# meteo-slave.net
KiCad netlist of a schematic drawn in EAGLE
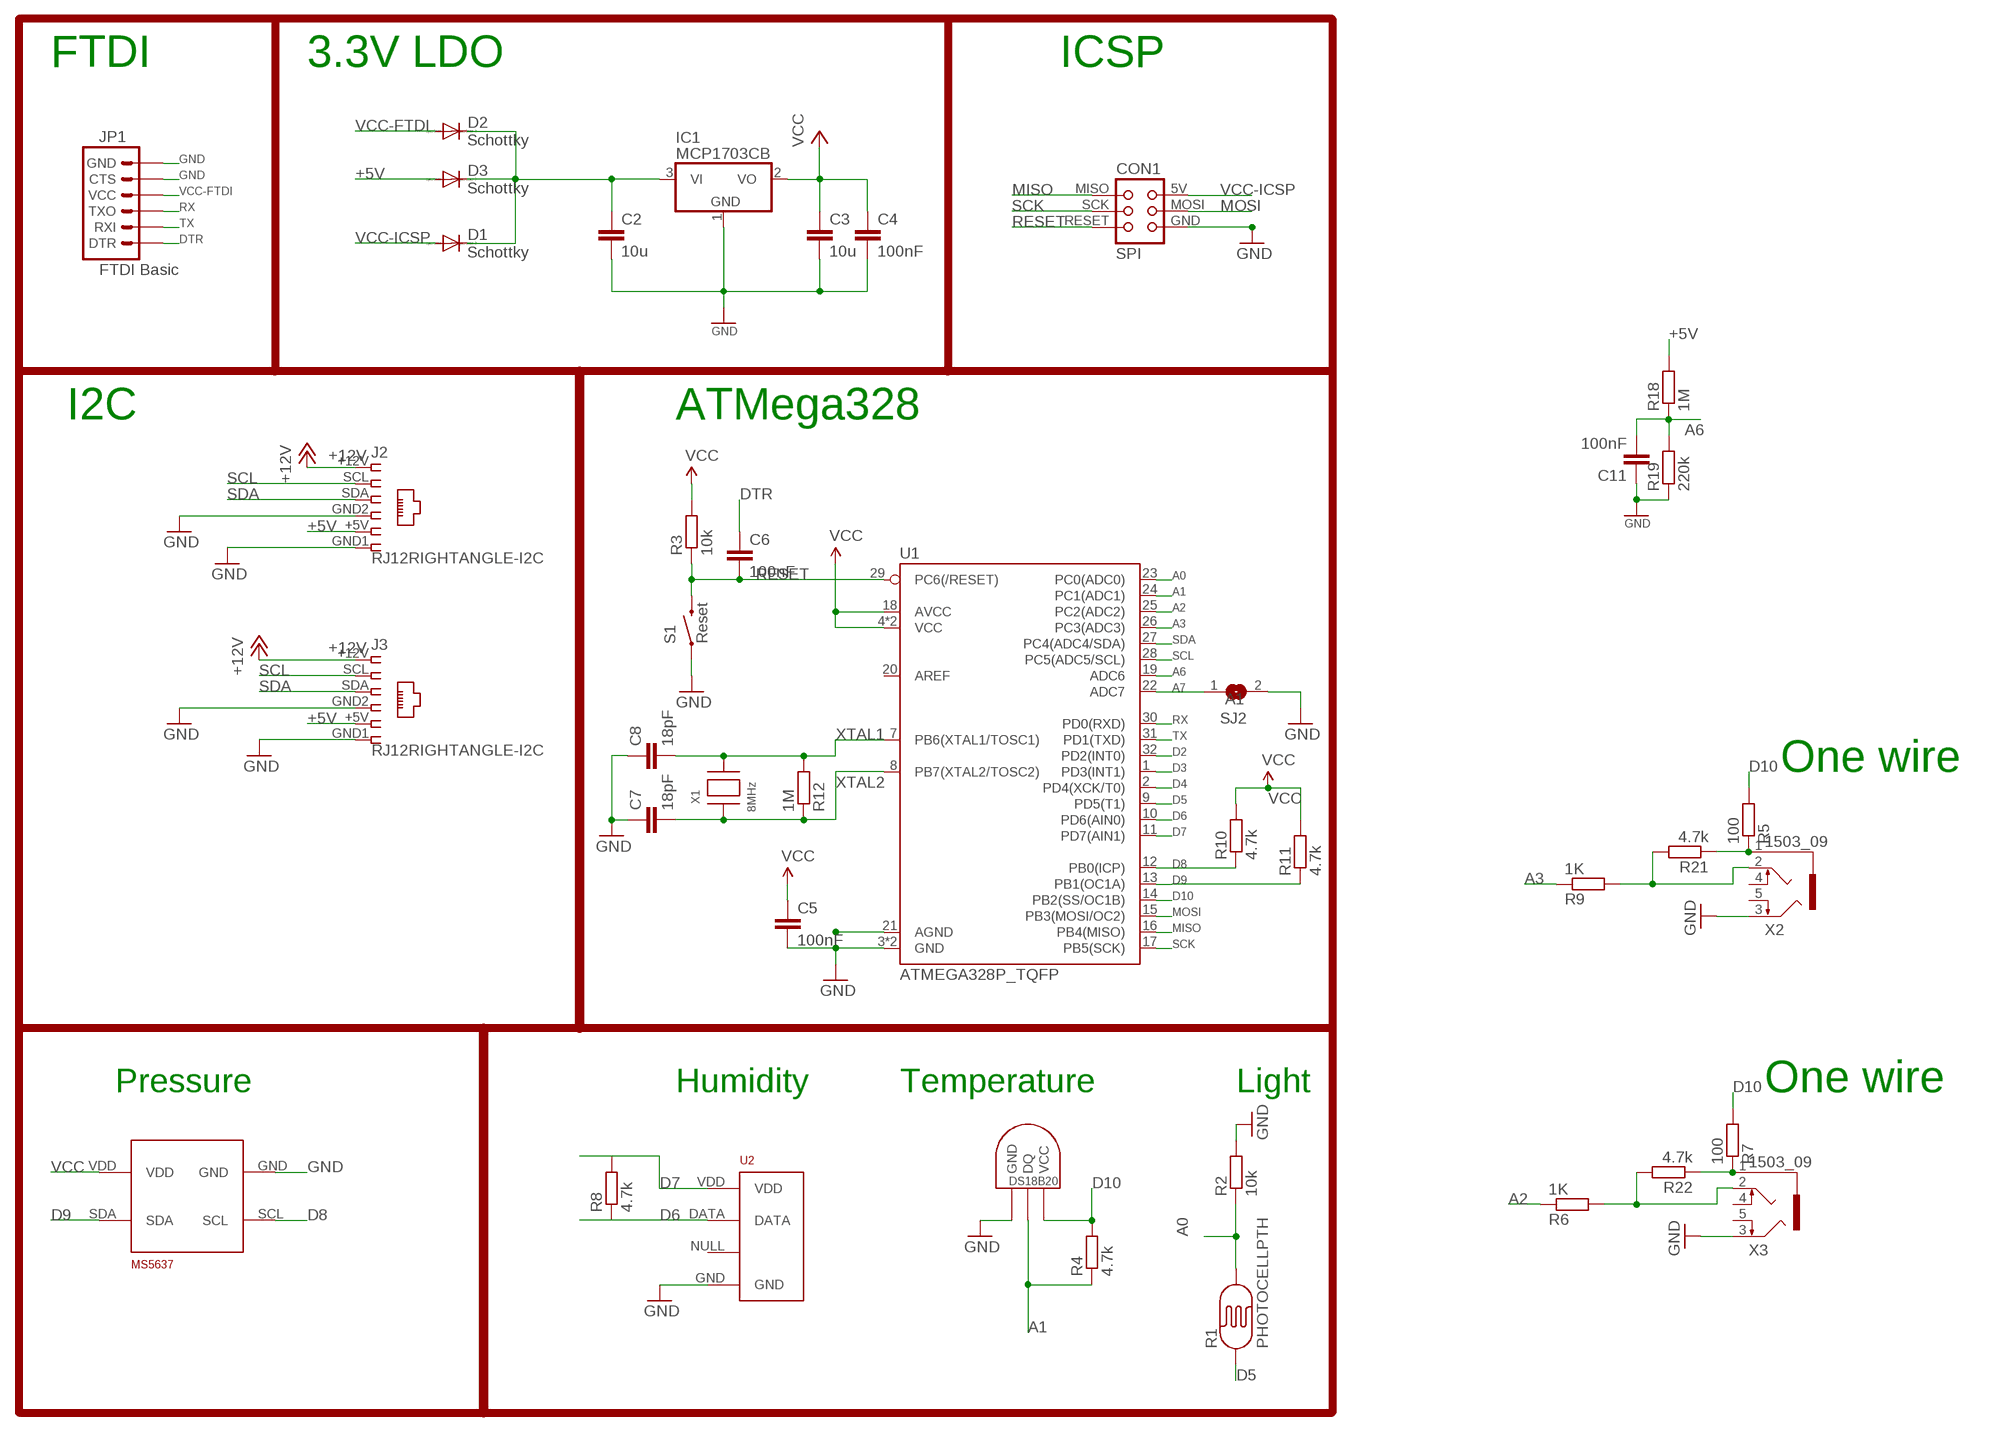
[diagram p0: schematic, sheet 1]

(export (version "E")
  (design (tool "Eeschema 10.0.6"))
  (components
    (comp (ref "C2")
      (value "10u")
      (footprint "eagle-import:C0805K")
      (fields (field (name "MPN") "77-VJ1206V106ZXQTBC"))
      (libsource (lib "eagle-import") (part "C-EUC0805K"))
    )
    (comp (ref "C3")
      (value "10u")
      (footprint "eagle-import:C0805K")
      (fields (field (name "MPN") "77-VJ1206V106ZXQTBC"))
      (libsource (lib "eagle-import") (part "C-EUC0805K"))
    )
    (comp (ref "C4")
      (value "100nF")
      (footprint "eagle-import:C0805K")
      (fields (field (name "MPN") "80-C1206C104K5R"))
      (libsource (lib "eagle-import") (part "C-EUC0805K"))
    )
    (comp (ref "C5")
      (value "100nF")
      (footprint "eagle-import:C0805K")
      (fields (field (name "MPN") "80-C1206C104K5R"))
      (libsource (lib "eagle-import") (part "C-EUC0805K"))
    )
    (comp (ref "C6")
      (value "100nF")
      (footprint "eagle-import:C0805K")
      (fields (field (name "MPN") "80-C1206C104K5R"))
      (libsource (lib "eagle-import") (part "C-EUC0805K"))
    )
    (comp (ref "C7")
      (value "18pF")
      (footprint "eagle-import:C0805K")
      (fields (field (name "MPN") "77-VJ1206A180JXXPBC"))
      (libsource (lib "eagle-import") (part "C-EUC0805K"))
    )
    (comp (ref "C8")
      (value "18pF")
      (footprint "eagle-import:C0805K")
      (fields (field (name "MPN") "77-VJ1206A180JXXPBC"))
      (libsource (lib "eagle-import") (part "C-EUC0805K"))
    )
    (comp (ref "C11")
      (value "100nF")
      (footprint "eagle-import:C0805K")
      (fields (field (name "MPN") "80-C1206C104K5R"))
      (libsource (lib "eagle-import") (part "C-EUC0805K"))
    )
    (comp (ref "CON1")
      (value "SPI")
      (footprint "eagle-import:TC2030-MCP")
      (libsource (lib "eagle-import") (part "TINYISPTAG"))
    )
    (comp (ref "D1")
      (value "Schottky")
      (footprint "eagle-import:SOD123")
      (fields (field (name "MPN") "621-1N5819HW-F"))
      (libsource (lib "eagle-import") (part "MBR0520LT"))
    )
    (comp (ref "D2")
      (value "Schottky")
      (footprint "eagle-import:SOD123")
      (fields (field (name "MPN") "621-1N5819HW-F"))
      (libsource (lib "eagle-import") (part "MBR0520LT"))
    )
    (comp (ref "D3")
      (value "Schottky")
      (footprint "eagle-import:SOD123")
      (fields (field (name "MPN") "621-1N5819HW-F"))
      (libsource (lib "eagle-import") (part "MBR0520LT"))
    )
    (comp (ref "IC1")
      (value "MCP1703CB")
      (footprint "eagle-import:SOT23")
      (libsource (lib "eagle-import") (part "MCP1703CB"))
    )
    (comp (ref "J2")
      (value "RJ12RIGHTANGLE-I2C")
      (footprint "eagle-import:RJ12-RIGHTANGLE-I2C")
      (libsource (lib "eagle-import") (part "RJ12RIGHTANGLE-I2C"))
    )
    (comp (ref "J3")
      (value "RJ12RIGHTANGLE-I2C")
      (footprint "eagle-import:RJ12-RIGHTANGLE-I2C")
      (libsource (lib "eagle-import") (part "RJ12RIGHTANGLE-I2C"))
    )
    (comp (ref "JP1")
      (value "FTDI Basic")
      (footprint "eagle-import:1X06")
      (libsource (lib "eagle-import") (part "ARDUINO_SERIAL_PROGRAMPTH"))
    )
    (comp (ref "R1")
      (value "PHOTOCELLPTH")
      (footprint "eagle-import:PHOTOCELL")
      (libsource (lib "eagle-import") (part "PHOTOCELLPTH"))
    )
    (comp (ref "R2")
      (value "10k")
      (footprint "eagle-import:R0805")
      (libsource (lib "eagle-import") (part "resistor_348_R-EU_R0805"))
    )
    (comp (ref "R3")
      (value "10k")
      (footprint "eagle-import:R0805")
      (libsource (lib "eagle-import") (part "R-EU_R0805"))
    )
    (comp (ref "R4")
      (value "4.7k")
      (footprint "eagle-import:R0805")
      (libsource (lib "eagle-import") (part "resistor_348_R-EU_R0805"))
    )
    (comp (ref "R5")
      (value "100")
      (footprint "eagle-import:R0805")
      (libsource (lib "eagle-import") (part "R-EU_R0805"))
    )
    (comp (ref "R6")
      (value "1K")
      (footprint "eagle-import:R0805")
      (libsource (lib "eagle-import") (part "R-EU_R0805"))
    )
    (comp (ref "R7")
      (value "100")
      (footprint "eagle-import:R0805")
      (libsource (lib "eagle-import") (part "R-EU_R0805"))
    )
    (comp (ref "R8")
      (value "4.7k")
      (footprint "eagle-import:R0805")
      (libsource (lib "eagle-import") (part "resistor_348_R-EU_R0805"))
    )
    (comp (ref "R9")
      (value "1K")
      (footprint "eagle-import:R0805")
      (libsource (lib "eagle-import") (part "R-EU_R0805"))
    )
    (comp (ref "R10")
      (value "4.7k")
      (footprint "eagle-import:R0805")
      (libsource (lib "eagle-import") (part "resistor_348_R-EU_R0805"))
    )
    (comp (ref "R11")
      (value "4.7k")
      (footprint "eagle-import:R0805")
      (libsource (lib "eagle-import") (part "resistor_348_R-EU_R0805"))
    )
    (comp (ref "R12")
      (value "1M")
      (footprint "eagle-import:R0805")
      (libsource (lib "eagle-import") (part "R-EU_R0805"))
    )
    (comp (ref "R18")
      (value "1M")
      (footprint "eagle-import:R0805")
      (libsource (lib "eagle-import") (part "R-EU_R0805"))
    )
    (comp (ref "R19")
      (value "220k")
      (footprint "eagle-import:R0805")
      (libsource (lib "eagle-import") (part "R-EU_R0805"))
    )
    (comp (ref "R21")
      (value "4.7k")
      (footprint "eagle-import:R0805")
      (libsource (lib "eagle-import") (part "resistor_R-EU_R0805"))
    )
    (comp (ref "R22")
      (value "4.7k")
      (footprint "eagle-import:R0805")
      (libsource (lib "eagle-import") (part "resistor_R-EU_R0805"))
    )
    (comp (ref "S1")
      (value "Reset")
      (footprint "eagle-import:TACTILE-SWITCH-SMD-ALT01")
      (libsource (lib "eagle-import") (part "SWITCH-MOMENTARY-2SMD-ALT01"))
    )
    (comp (ref "SJ2") (value "A1") (footprint "eagle-import:SJ") (libsource (lib "eagle-import") (part "SJ")))
    (comp (ref "U$1")
      (value "DS1820TO92")
      (footprint "eagle-import:DS1820")
      (libsource (lib "eagle-import") (part "DS1820TO92"))
    )
    (comp (ref "U$19")
      (value "MS5637WIDE")
      (footprint "eagle-import:MS5637WIDE")
      (libsource (lib "eagle-import") (part "MS5637WIDE"))
    )
    (comp (ref "U1")
      (value "ATMEGA328P_TQFP")
      (footprint "eagle-import:TQFP32-08")
      (libsource (lib "eagle-import") (part "ATMEGA328P_TQFP"))
    )
    (comp (ref "U2")
      (value "RHT03_DHT-22_AM2302")
      (footprint "eagle-import:RHT03_DHT-22")
      (libsource (lib "eagle-import") (part "RHT03_DHT-22_AM2302"))
    )
    (comp (ref "X1")
      (value "8MHz")
      (footprint "eagle-import:NX6035")
      (fields (field (name "MPN") "729-F60800010"))
      (libsource (lib "eagle-import") (part "XTALNX6035"))
    )
    (comp (ref "X2")
      (value "1503_09")
      (footprint "eagle-import:1503_09")
      (libsource (lib "eagle-import") (part "1503_09"))
    )
    (comp (ref "X3")
      (value "1503_09")
      (footprint "eagle-import:1503_09")
      (libsource (lib "eagle-import") (part "1503_09"))
    )
  )
  (nets
    (net (code "1") (name "+5V") (class "Default")
      (node (ref "D3") (pin "A") (pinfunction "A_A") (pintype "passive"))
      (node (ref "J2") (pin "+5V") (pinfunction "5_+5V") (pintype "bidirectional"))
      (node (ref "J3") (pin "+5V") (pinfunction "5_+5V") (pintype "bidirectional"))
      (node (ref "R18") (pin "2") (pinfunction "2_2") (pintype "passive"))
    )
    (net (code "2") (name "+12V") (class "Default")
      (node (ref "J2") (pin "+12V") (pinfunction "1_+12V") (pintype "bidirectional"))
      (node (ref "J3") (pin "+12V") (pinfunction "1_+12V") (pintype "bidirectional"))
    )
    (net (code "3") (name "A0") (class "Default")
      (node (ref "R1") (pin "2") (pinfunction "P$2_2") (pintype "bidirectional"))
      (node (ref "R2") (pin "1") (pinfunction "1_1") (pintype "passive"))
      (node (ref "U1") (pin "23") (pinfunction "PC0(ADC0)_23") (pintype "bidirectional"))
    )
    (net (code "4") (name "A1") (class "Default")
      (node (ref "R4") (pin "1") (pinfunction "1_1") (pintype "passive"))
      (node (ref "U$1") (pin "DQ") (pinfunction "DQ_DQ") (pintype "bidirectional"))
      (node (ref "U1") (pin "24") (pinfunction "PC1(ADC1)_24") (pintype "bidirectional"))
    )
    (net (code "5") (name "A2") (class "Default")
      (node (ref "R6") (pin "1") (pinfunction "1_1") (pintype "passive"))
      (node (ref "U1") (pin "25") (pinfunction "PC2(ADC2)_25") (pintype "bidirectional"))
    )
    (net (code "6") (name "A3") (class "Default")
      (node (ref "R9") (pin "1") (pinfunction "1_1") (pintype "passive"))
      (node (ref "U1") (pin "26") (pinfunction "PC3(ADC3)_26") (pintype "bidirectional"))
    )
    (net (code "7") (name "A6") (class "Default")
      (node (ref "C11") (pin "2") (pinfunction "2_2") (pintype "passive"))
      (node (ref "R18") (pin "1") (pinfunction "1_1") (pintype "passive"))
      (node (ref "R19") (pin "2") (pinfunction "2_2") (pintype "passive"))
      (node (ref "U1") (pin "19") (pinfunction "ADC6_19") (pintype "bidirectional"))
    )
    (net (code "8") (name "A7") (class "Default")
      (node (ref "SJ2") (pin "1") (pinfunction "1_1") (pintype "passive"))
      (node (ref "U1") (pin "22") (pinfunction "ADC7_22") (pintype "bidirectional"))
    )
    (net (code "9") (name "D2") (class "Default")
      (node (ref "U1") (pin "32") (pinfunction "PD2(INT0)_32") (pintype "bidirectional"))
    )
    (net (code "10") (name "D3") (class "Default")
      (node (ref "U1") (pin "1") (pinfunction "PD3(INT1)_1") (pintype "bidirectional"))
    )
    (net (code "11") (name "D4") (class "Default")
      (node (ref "U1") (pin "2") (pinfunction "PD4(XCK/T0)_2") (pintype "bidirectional"))
    )
    (net (code "12") (name "D5") (class "Default")
      (node (ref "R1") (pin "1") (pinfunction "P$1_1") (pintype "bidirectional"))
      (node (ref "U1") (pin "9") (pinfunction "PD5(T1)_9") (pintype "bidirectional"))
    )
    (net (code "13") (name "D6") (class "Default")
      (node (ref "R8") (pin "1") (pinfunction "1_1") (pintype "passive"))
      (node (ref "U1") (pin "10") (pinfunction "PD6(AIN0)_10") (pintype "bidirectional"))
      (node (ref "U2") (pin "DATA") (pinfunction "DATA_DATA") (pintype "bidirectional"))
    )
    (net (code "14") (name "D7") (class "Default")
      (node (ref "R8") (pin "2") (pinfunction "2_2") (pintype "passive"))
      (node (ref "U1") (pin "11") (pinfunction "PD7(AIN1)_11") (pintype "bidirectional"))
      (node (ref "U2") (pin "VDD") (pinfunction "VDD_VDD") (pintype "power_in"))
    )
    (net (code "15") (name "D8") (class "Default")
      (node (ref "R10") (pin "1") (pinfunction "1_1") (pintype "passive"))
      (node (ref "U$19") (pin "SCL") (pinfunction "SCL_SCL") (pintype "bidirectional"))
      (node (ref "U1") (pin "12") (pinfunction "PB0(ICP)_12") (pintype "bidirectional"))
    )
    (net (code "16") (name "D9") (class "Default")
      (node (ref "R11") (pin "1") (pinfunction "1_1") (pintype "passive"))
      (node (ref "U$19") (pin "SDA") (pinfunction "SDA_SDA") (pintype "bidirectional"))
      (node (ref "U1") (pin "13") (pinfunction "PB1(OC1A)_13") (pintype "bidirectional"))
    )
    (net (code "17") (name "D10") (class "Default")
      (node (ref "R4") (pin "2") (pinfunction "2_2") (pintype "passive"))
      (node (ref "R5") (pin "2") (pinfunction "2_2") (pintype "passive"))
      (node (ref "R7") (pin "2") (pinfunction "2_2") (pintype "passive"))
      (node (ref "U$1") (pin "VDD") (pinfunction "VCC_VDD") (pintype "power_in"))
      (node (ref "U1") (pin "14") (pinfunction "PB2(SS/OC1B)_14") (pintype "bidirectional"))
    )
    (net (code "18") (name "DTR") (class "Default")
      (node (ref "C6") (pin "1") (pinfunction "1_1") (pintype "passive"))
      (node (ref "JP1") (pin "1") (pinfunction "DTR_1") (pintype "passive"))
    )
    (net (code "19") (name "GND") (class "Default")
      (node (ref "C11") (pin "1") (pinfunction "1_1") (pintype "passive"))
      (node (ref "C2") (pin "2") (pinfunction "2_2") (pintype "passive"))
      (node (ref "C3") (pin "2") (pinfunction "2_2") (pintype "passive"))
      (node (ref "C4") (pin "2") (pinfunction "2_2") (pintype "passive"))
      (node (ref "C5") (pin "2") (pinfunction "2_2") (pintype "passive"))
      (node (ref "C7") (pin "1") (pinfunction "1_1") (pintype "passive"))
      (node (ref "C8") (pin "1") (pinfunction "1_1") (pintype "passive"))
      (node (ref "CON1") (pin "GND") (pinfunction "GND_GND") (pintype "passive"))
      (node (ref "IC1") (pin "1") (pinfunction "GND_1") (pintype "passive"))
      (node (ref "J2") (pin "GND1") (pinfunction "6_GND1") (pintype "bidirectional"))
      (node (ref "J2") (pin "GND2") (pinfunction "4_GND2") (pintype "bidirectional"))
      (node (ref "J3") (pin "GND1") (pinfunction "6_GND1") (pintype "bidirectional"))
      (node (ref "J3") (pin "GND2") (pinfunction "4_GND2") (pintype "bidirectional"))
      (node (ref "JP1") (pin "5") (pinfunction "CTS_5") (pintype "passive"))
      (node (ref "JP1") (pin "6") (pinfunction "GND_6") (pintype "passive"))
      (node (ref "R19") (pin "1") (pinfunction "1_1") (pintype "passive"))
      (node (ref "R2") (pin "2") (pinfunction "2_2") (pintype "passive"))
      (node (ref "S1") (pin "1") (pinfunction "1_1") (pintype "passive"))
      (node (ref "S1") (pin "2") (pinfunction "1_2") (pintype "passive"))
      (node (ref "SJ2") (pin "2") (pinfunction "2_2") (pintype "passive"))
      (node (ref "U$1") (pin "GND") (pinfunction "GND_GND") (pintype "power_in"))
      (node (ref "U$19") (pin "GND") (pinfunction "GND_GND") (pintype "bidirectional"))
      (node (ref "U1") (pin "21") (pinfunction "AGND_21") (pintype "bidirectional"))
      (node (ref "U1") (pin "3") (pinfunction "GND_3") (pintype "bidirectional"))
      (node (ref "U1") (pin "5") (pinfunction "GND_5") (pintype "bidirectional"))
      (node (ref "U2") (pin "GND") (pinfunction "GND_GND") (pintype "power_in"))
      (node (ref "X2") (pin "3") (pinfunction "3_3") (pintype "passive"))
      (node (ref "X3") (pin "3") (pinfunction "3_3") (pintype "passive"))
    )
    (net (code "20") (name "MISO") (class "Default")
      (node (ref "CON1") (pin "MISO") (pinfunction "MISO_MISO") (pintype "passive"))
      (node (ref "U1") (pin "16") (pinfunction "PB4(MISO)_16") (pintype "bidirectional"))
    )
    (net (code "21") (name "MOSI") (class "Default")
      (node (ref "CON1") (pin "MOSI") (pinfunction "MOSI_MOSI") (pintype "passive"))
      (node (ref "U1") (pin "15") (pinfunction "PB3(MOSI/OC2)_15") (pintype "bidirectional"))
    )
    (net (code "22") (name "Net-(IC1-VI)") (class "Default")
      (node (ref "C2") (pin "1") (pinfunction "1_1") (pintype "passive"))
      (node (ref "D1") (pin "C") (pinfunction "C_C") (pintype "passive"))
      (node (ref "D2") (pin "C") (pinfunction "C_C") (pintype "passive"))
      (node (ref "D3") (pin "C") (pinfunction "C_C") (pintype "passive"))
      (node (ref "IC1") (pin "3") (pinfunction "VI_3") (pintype "input"))
    )
    (net (code "23") (name "Net-(R21-Pad1)") (class "Default")
      (node (ref "R21") (pin "1") (pinfunction "1_1") (pintype "passive"))
      (node (ref "R5") (pin "1") (pinfunction "1_1") (pintype "passive"))
      (node (ref "X2") (pin "1") (pinfunction "1_1") (pintype "passive"))
    )
    (net (code "24") (name "Net-(R21-Pad2)") (class "Default")
      (node (ref "R21") (pin "2") (pinfunction "2_2") (pintype "passive"))
      (node (ref "R9") (pin "2") (pinfunction "2_2") (pintype "passive"))
      (node (ref "X2") (pin "2") (pinfunction "2_2") (pintype "passive"))
    )
    (net (code "25") (name "Net-(R22-Pad1)") (class "Default")
      (node (ref "R22") (pin "1") (pinfunction "1_1") (pintype "passive"))
      (node (ref "R7") (pin "1") (pinfunction "1_1") (pintype "passive"))
      (node (ref "X3") (pin "1") (pinfunction "1_1") (pintype "passive"))
    )
    (net (code "26") (name "Net-(R22-Pad2)") (class "Default")
      (node (ref "R22") (pin "2") (pinfunction "2_2") (pintype "passive"))
      (node (ref "R6") (pin "2") (pinfunction "2_2") (pintype "passive"))
      (node (ref "X3") (pin "2") (pinfunction "2_2") (pintype "passive"))
    )
    (net (code "27") (name "RESET") (class "Default")
      (node (ref "C6") (pin "2") (pinfunction "2_2") (pintype "passive"))
      (node (ref "CON1") (pin "RESET") (pinfunction "RESET_RESET") (pintype "passive"))
      (node (ref "R3") (pin "1") (pinfunction "1_1") (pintype "passive"))
      (node (ref "S1") (pin "3") (pinfunction "2_3") (pintype "passive"))
      (node (ref "S1") (pin "4") (pinfunction "2_4") (pintype "passive"))
      (node (ref "U1") (pin "29") (pinfunction "PC6(/RESET)_29") (pintype "bidirectional"))
    )
    (net (code "28") (name "RX") (class "Default")
      (node (ref "JP1") (pin "3") (pinfunction "TXO_3") (pintype "passive"))
      (node (ref "U1") (pin "30") (pinfunction "PD0(RXD)_30") (pintype "bidirectional"))
    )
    (net (code "29") (name "SCK") (class "Default")
      (node (ref "CON1") (pin "SCK") (pinfunction "SCK_SCK") (pintype "passive"))
      (node (ref "U1") (pin "17") (pinfunction "PB5(SCK)_17") (pintype "bidirectional"))
    )
    (net (code "30") (name "SCL") (class "Default")
      (node (ref "J2") (pin "SCL") (pinfunction "2_SCL") (pintype "bidirectional"))
      (node (ref "J3") (pin "SCL") (pinfunction "2_SCL") (pintype "bidirectional"))
      (node (ref "U1") (pin "28") (pinfunction "PC5(ADC5/SCL)_28") (pintype "bidirectional"))
    )
    (net (code "31") (name "SDA") (class "Default")
      (node (ref "J2") (pin "SDA") (pinfunction "3_SDA") (pintype "bidirectional"))
      (node (ref "J3") (pin "SDA") (pinfunction "3_SDA") (pintype "bidirectional"))
      (node (ref "U1") (pin "27") (pinfunction "PC4(ADC4/SDA)_27") (pintype "bidirectional"))
    )
    (net (code "32") (name "TX") (class "Default")
      (node (ref "JP1") (pin "2") (pinfunction "RXI_2") (pintype "passive"))
      (node (ref "U1") (pin "31") (pinfunction "PD1(TXD)_31") (pintype "bidirectional"))
    )
    (net (code "33") (name "VCC") (class "Default")
      (node (ref "C3") (pin "1") (pinfunction "1_1") (pintype "passive"))
      (node (ref "C4") (pin "1") (pinfunction "1_1") (pintype "passive"))
      (node (ref "C5") (pin "1") (pinfunction "1_1") (pintype "passive"))
      (node (ref "IC1") (pin "2") (pinfunction "VO_2") (pintype "passive"))
      (node (ref "R10") (pin "2") (pinfunction "2_2") (pintype "passive"))
      (node (ref "R11") (pin "2") (pinfunction "2_2") (pintype "passive"))
      (node (ref "R3") (pin "2") (pinfunction "2_2") (pintype "passive"))
      (node (ref "U$19") (pin "VDD") (pinfunction "VDD_VDD") (pintype "bidirectional"))
      (node (ref "U1") (pin "18") (pinfunction "AVCC_18") (pintype "bidirectional"))
      (node (ref "U1") (pin "4") (pinfunction "VCC_4") (pintype "bidirectional"))
      (node (ref "U1") (pin "6") (pinfunction "VCC_6") (pintype "bidirectional"))
    )
    (net (code "34") (name "VCC-FTDI") (class "Default")
      (node (ref "D2") (pin "A") (pinfunction "A_A") (pintype "passive"))
      (node (ref "JP1") (pin "4") (pinfunction "VCC_4") (pintype "passive"))
    )
    (net (code "35") (name "VCC-ICSP") (class "Default")
      (node (ref "CON1") (pin "5V") (pinfunction "VCC_5V") (pintype "passive"))
      (node (ref "D1") (pin "A") (pinfunction "A_A") (pintype "passive"))
    )
    (net (code "36") (name "XTAL1") (class "Default")
      (node (ref "C8") (pin "2") (pinfunction "2_2") (pintype "passive"))
      (node (ref "R12") (pin "2") (pinfunction "2_2") (pintype "passive"))
      (node (ref "U1") (pin "7") (pinfunction "PB6(XTAL1/TOSC1)_7") (pintype "bidirectional"))
      (node (ref "X1") (pin "P$2") (pinfunction "P$2_P$2") (pintype "bidirectional"))
    )
    (net (code "37") (name "XTAL2") (class "Default")
      (node (ref "C7") (pin "2") (pinfunction "2_2") (pintype "passive"))
      (node (ref "R12") (pin "1") (pinfunction "1_1") (pintype "passive"))
      (node (ref "U1") (pin "8") (pinfunction "PB7(XTAL2/TOSC2)_8") (pintype "bidirectional"))
      (node (ref "X1") (pin "P$1") (pinfunction "P$1_P$1") (pintype "bidirectional"))
    )
    (net (code "38") (name "unconnected-(U1-AREF-Pad20)") (class "Default")
      (node (ref "U1") (pin "20") (pinfunction "AREF_20") (pintype "bidirectional"))
    )
    (net (code "39") (name "unconnected-(U2-PadNULL)") (class "Default")
      (node (ref "U2") (pin "NULL") (pinfunction "NULL_NULL") (pintype "no_connect"))
    )
    (net (code "40") (name "unconnected-(X2-Pad4)") (class "Default")
      (node (ref "X2") (pin "4") (pinfunction "4_4") (pintype "passive"))
    )
    (net (code "41") (name "unconnected-(X2-Pad5)") (class "Default")
      (node (ref "X2") (pin "5") (pinfunction "5_5") (pintype "passive"))
    )
    (net (code "42") (name "unconnected-(X3-Pad4)") (class "Default")
      (node (ref "X3") (pin "4") (pinfunction "4_4") (pintype "passive"))
    )
    (net (code "43") (name "unconnected-(X3-Pad5)") (class "Default")
      (node (ref "X3") (pin "5") (pinfunction "5_5") (pintype "passive"))
    )
  )
)
